# Sense_6_Signal_Isolation.net
KiCad netlist of a schematic drawn in Altium Designer
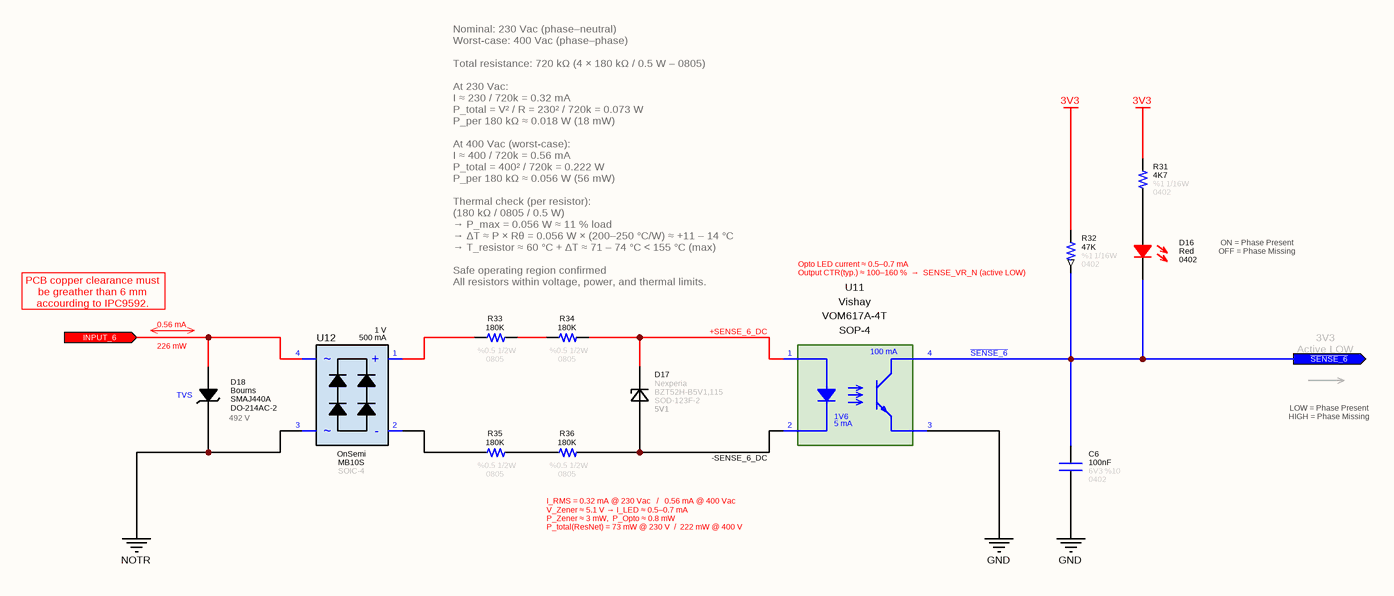
[diagram p0: Sense 6 Signal Isolation.SchDoc]

(export (version "E")
  (design (tool "Eeschema 10.0.6"))
  (components
    (comp (ref "C6")
      (value "100nF")
      (footprint "CAPACITOR_0402")
      (description "Capacitor (MLCC) - 100nF / 6V3 / 0402")
      (fields
        (field (name "MANUFACTURER PART NUMBER") "04026D104KAT4A")
        (field (name "TOLERANCE") "%10")
        (field (name "VOLTAGE") "6V3")
        (field (name "CASE") "0402")
        (field (name "Comment") "Capacitor - 100nF [0402] (MLCC)")
      )
      (libsource (lib "Akkoyun") (part "Capacitor - 100nF [0402-6V3]"))
    )
    (comp (ref "D16")
      (value "SMD LED (Red)")
      (footprint "LED_0402")
      (description "Standard LEDs - SMD MINI-MOLD ULTRA COMPACT RED")
      (fields
        (field (name "MANUFACTURER PART NUMBER") "SML-P12VTT86R")
        (field (name "CASE") "0402")
        (field (name "COLOR") "Red")
      )
      (libsource (lib "Akkoyun") (part "Diode - LED (0402-Red)"))
    )
    (comp (ref "D17")
      (value "BZT52H-B5V1,115")
      (footprint "SOD-123F-2")
      (description "Zener Diodes BZT52H-B5V1/SOD123F/SOD2")
      (fields
        (field (name "ZENER VOLTAGE") "5V1")
        (field (name "MANUFACTURER NAME") "Nexperia")
        (field (name "MANUFACTURER PART NUMBER") "BZT52H-B5V1,115")
        (field (name "CASE") "SOD-123F-2")
      )
      (libsource (lib "Akkoyun") (part "Diode - BZT52H-B5V1,115"))
    )
    (comp (ref "D18")
      (value "SMAJ440A")
      (footprint "DO-220AA-2")
      (description "ESD Protection Diodes / TVS Diodes 440volts 1uA .6 Amps Uni-Dir")
      (fields
        (field (name "BREAKDOWN VOLTAGE") "492 V")
        (field (name "MANUFACTURER NAME") "Bourns")
        (field (name "MANUFACTURER PART NUMBER") "SMAJ440A")
        (field (name "CASE") "DO-214AC-2")
      )
      (libsource (lib "Akkoyun") (part "Diode - SMAJ440A (TVS)"))
    )
    (comp (ref "R31")
      (value "4K7")
      (footprint "RESISTOR_0402")
      (description "Thick Film Resistors - SMD 1/16 W 4.7 KOhm 1%")
      (fields
        (field (name "MANUFACTURER PART NUMBER") "CRCW04024K70FKED")
        (field (name "TOLERANCE") "%1")
        (field (name "CASE") "0402")
        (field (name "POWER") "1/16W")
        (field (name "Comment") "4K7 - 0402 - %1 - 1/16W")
      )
      (libsource (lib "Akkoyun") (part "Resistor - 4K7 [0402]"))
    )
    (comp (ref "R32")
      (value "47K")
      (footprint "RESISTOR_0402")
      (description "Thick Film Resistors - SMD 1/16 W 47 KOhm 1%")
      (fields
        (field (name "MANUFACTURER PART NUMBER") "CRCW040247K0FKED")
        (field (name "TOLERANCE") "%1")
        (field (name "CASE") "0402")
        (field (name "POWER") "1/16W")
        (field (name "Comment") "47K - 0402 - %1 - 1/16W")
      )
      (libsource (lib "Akkoyun") (part "Resistor - 47K [0402]"))
    )
    (comp (ref "R33")
      (value "180K")
      (footprint "RESISTOR_0805")
      (description "Thick Film Resistors - SMD 0805 180Kohms 0.5W 0.5% AEC-Q200")
      (fields
        (field (name "MANUFACTURER PART NUMBER") "ERJ-P06D1803V")
        (field (name "TOLERANCE") "%0.5")
        (field (name "CASE") "0805")
        (field (name "POWER") "1/2W")
        (field (name "Comment") "180K - 0805 - %0.5 - 1/2W")
      )
      (libsource (lib "Akkoyun") (part "Resistor - 180K [0805]"))
    )
    (comp (ref "R34")
      (value "180K")
      (footprint "RESISTOR_0805")
      (description "Thick Film Resistors - SMD 0805 180Kohms 0.5W 0.5% AEC-Q200")
      (fields
        (field (name "MANUFACTURER PART NUMBER") "ERJ-P06D1803V")
        (field (name "TOLERANCE") "%0.5")
        (field (name "CASE") "0805")
        (field (name "POWER") "1/2W")
        (field (name "Comment") "180K - 0805 - %0.5 - 1/2W")
      )
      (libsource (lib "Akkoyun") (part "Resistor - 180K [0805]"))
    )
    (comp (ref "R35")
      (value "180K")
      (footprint "RESISTOR_0805")
      (description "Thick Film Resistors - SMD 0805 180Kohms 0.5W 0.5% AEC-Q200")
      (fields
        (field (name "MANUFACTURER PART NUMBER") "ERJ-P06D1803V")
        (field (name "TOLERANCE") "%0.5")
        (field (name "CASE") "0805")
        (field (name "POWER") "1/2W")
        (field (name "Comment") "180K - 0805 - %0.5 - 1/2W")
      )
      (libsource (lib "Akkoyun") (part "Resistor - 180K [0805]"))
    )
    (comp (ref "R36")
      (value "180K")
      (footprint "RESISTOR_0805")
      (description "Thick Film Resistors - SMD 0805 180Kohms 0.5W 0.5% AEC-Q200")
      (fields
        (field (name "MANUFACTURER PART NUMBER") "ERJ-P06D1803V")
        (field (name "TOLERANCE") "%0.5")
        (field (name "CASE") "0805")
        (field (name "POWER") "1/2W")
        (field (name "Comment") "180K - 0805 - %0.5 - 1/2W")
      )
      (libsource (lib "Akkoyun") (part "Resistor - 180K [0805]"))
    )
    (comp (ref "U11")
      (value "VOM617A-4T")
      (footprint "SOP-4V2")
      (description "Transistor Output Optocouplers Phototransistor Out CTR 160-320% 5mA")
      (fields
        (field (name "MANUFACTURER PART NUMBER") "VOM617A-4T")
        (field (name "MANUFACTURER NAME") "Vishay")
        (field (name "CASE") "SOP-4")
        (field (name "IF - FORWARD CURRENT") "5 mA")
        (field (name "VF - FORWARD VOLTAGE") "1V6")
        (field (name "MAXIMUM COLLECTOR CURRENT") "100 mA")
      )
      (libsource (lib "Akkoyun") (part "IC - VOM617A"))
    )
    (comp (ref "U12")
      (value "LTV-846S")
      (footprint "SOIC-4")
      (description "Transistor Output Optocouplers Optocplr Phototrans 4-Channel")
      (fields
        (field (name "IF - FORWARD CURRENT") "500 mA")
        (field (name "VF - FORWARD VOLTAGE") "1 V")
        (field (name "MANUFACTURER NAME") "OnSemi")
        (field (name "MANUFACTURER PART NUMBER") "MB10S")
        (field (name "CASE") "SOIC-4")
      )
      (libsource (lib "Akkoyun") (part "IC - MB10S"))
    )
  )
  (nets
    (net (code "1") (name "/+SENSE_6_DC") (class "Default")
      (node (ref "D17") (pin "1") (pinfunction "Cathode_1") (pintype "passive"))
      (node (ref "R34") (pin "1") (pinfunction "1_1") (pintype "passive"))
      (node (ref "U11") (pin "1") (pinfunction "LED_Anode_1") (pintype "passive"))
    )
    (net (code "2") (name "/-SENSE_6_DC") (class "Default")
      (node (ref "D17") (pin "2") (pinfunction "Anode_2") (pintype "passive"))
      (node (ref "R36") (pin "1") (pinfunction "1_1") (pintype "passive"))
      (node (ref "U11") (pin "2") (pinfunction "LED_Cathode_2") (pintype "passive"))
    )
    (net (code "3") (name "/INPUT_6") (class "Default")
      (node (ref "D18") (pin "1") (pinfunction "Anode_1") (pintype "passive"))
      (node (ref "U12") (pin "4") (pinfunction "~_4") (pintype "passive"))
    )
    (net (code "4") (name "/~{SENSE_6}") (class "Default")
      (node (ref "C6") (pin "2") (pinfunction "2_2") (pintype "passive"))
      (node (ref "D16") (pin "1") (pinfunction "1_1") (pintype "passive"))
      (node (ref "R32") (pin "1") (pinfunction "1_1") (pintype "output"))
      (node (ref "U11") (pin "4") (pinfunction "Collector_4") (pintype "passive"))
    )
    (net (code "5") (name "3V3") (class "Default")
      (node (ref "R31") (pin "2") (pinfunction "2_2") (pintype "passive"))
      (node (ref "R32") (pin "2") (pinfunction "2_2") (pintype "passive"))
    )
    (net (code "6") (name "GND") (class "Default")
      (node (ref "C6") (pin "1") (pinfunction "1_1") (pintype "passive"))
      (node (ref "U11") (pin "3") (pinfunction "Emiter_3") (pintype "passive"))
    )
    (net (code "7") (name "NOTR") (class "Default")
      (node (ref "D18") (pin "2") (pinfunction "Cathode_2") (pintype "passive"))
      (node (ref "U12") (pin "3") (pinfunction "~_3") (pintype "passive"))
    )
    (net (code "8") (name "Net-(D16-Pad2)") (class "Default")
      (node (ref "D16") (pin "2") (pinfunction "2_2") (pintype "passive"))
      (node (ref "R31") (pin "1") (pinfunction "1_1") (pintype "passive"))
    )
    (net (code "9") (name "Net-(R33-Pad1)") (class "Default")
      (node (ref "R33") (pin "1") (pinfunction "1_1") (pintype "passive"))
      (node (ref "R34") (pin "2") (pinfunction "2_2") (pintype "passive"))
    )
    (net (code "10") (name "Net-(R35-Pad1)") (class "Default")
      (node (ref "R35") (pin "1") (pinfunction "1_1") (pintype "passive"))
      (node (ref "R36") (pin "2") (pinfunction "2_2") (pintype "passive"))
    )
    (net (code "11") (name "Net-(U12-+)") (class "Default")
      (node (ref "R33") (pin "2") (pinfunction "2_2") (pintype "passive"))
      (node (ref "U12") (pin "1") (pinfunction "+_1") (pintype "passive"))
    )
    (net (code "12") (name "Net-(U12--)") (class "Default")
      (node (ref "R35") (pin "2") (pinfunction "2_2") (pintype "passive"))
      (node (ref "U12") (pin "2") (pinfunction "-_2") (pintype "passive"))
    )
  )
)
